# BMI088.net
KiCad netlist of a schematic drawn in Altium Designer
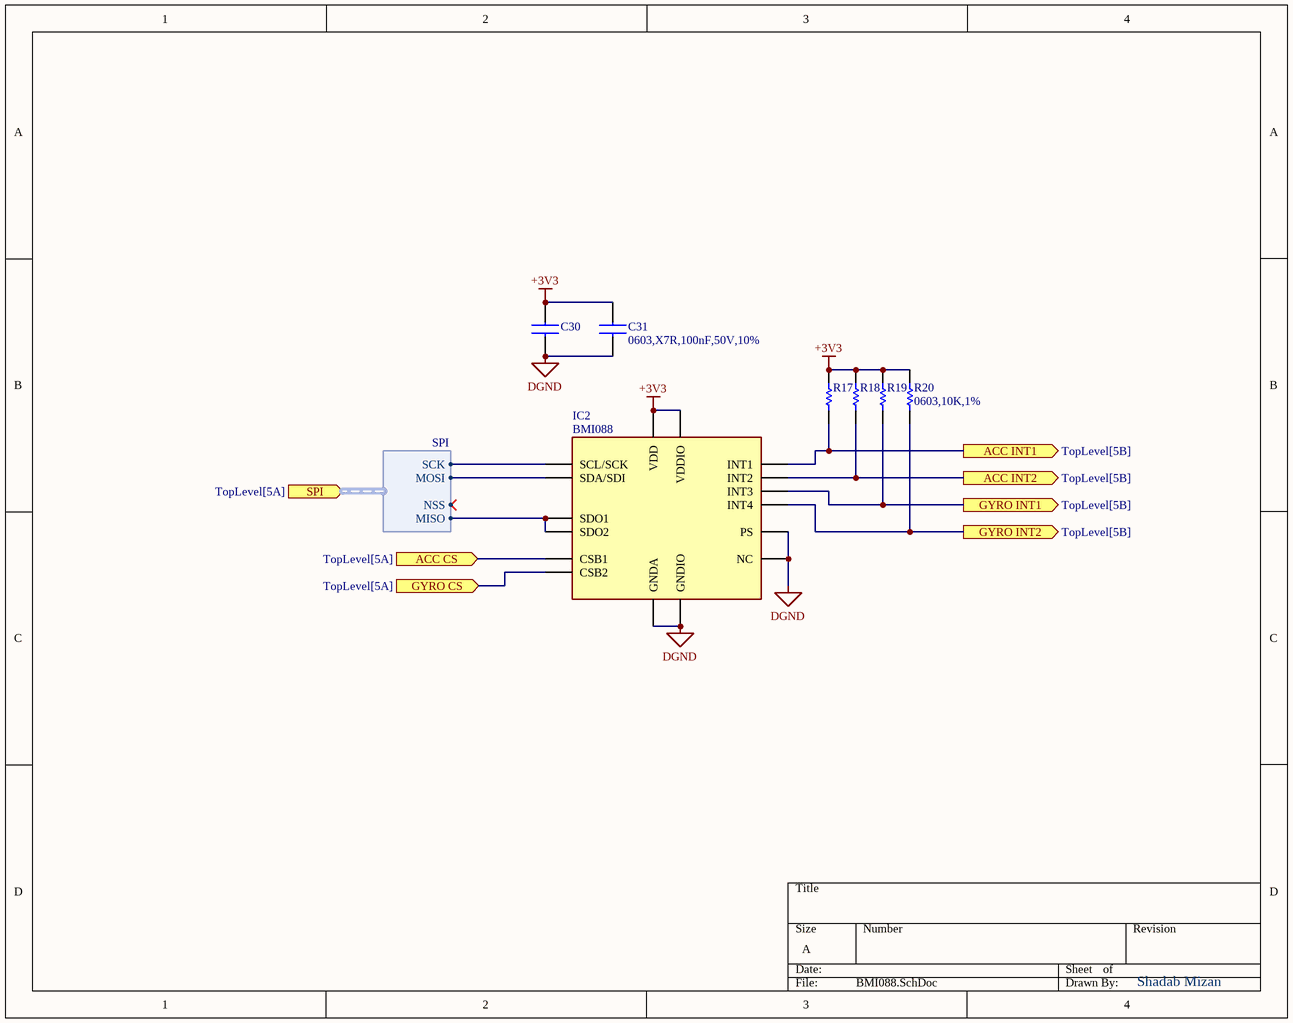
[diagram p0: BMI088.SchDoc]

(export (version "E")
  (design (tool "Eeschema 10.0.6"))
  (components
    (comp (ref "C30")
      (value "0603,X7R,100nF,50V,10%")
      (footprint "CAPC1608X90N")
      (description "50V 100nF X7R ±10% 0603 Multilayer Ceramic Capacitors MLCC - SMD/SMT ROHS")
      (fields (field (name "LCSC PART #") "C14663") (field (name "MANU PART #") "CC0603KRX7R9BB104"))
      (libsource (lib "flight-controller") (part "CC0603KRX7R9BB104"))
    )
    (comp (ref "C31")
      (value "0603,X7R,100nF,50V,10%")
      (footprint "CAPC1608X90N")
      (description "50V 100nF X7R ±10% 0603 Multilayer Ceramic Capacitors MLCC - SMD/SMT ROHS")
      (fields (field (name "LCSC PART #") "C14663") (field (name "MANU PART #") "CC0603KRX7R9BB104"))
      (libsource (lib "flight-controller") (part "CC0603KRX7R9BB104"))
    )
    (comp (ref "IC2")
      (value "BMI088")
      (footprint "BMI088")
      (description "Inertial Measurement Unit IMU 6-Axis LGA")
      (fields (field (name "LCSC PART #") "C194919"))
      (libsource (lib "flight-controller") (part "BMI088"))
    )
    (comp (ref "R17")
      (value "0603,10K,1%")
      (footprint "RESC1608X90N")
      (description "100mW Thick Film Resistor 75V ±100ppm/℃ ±1% 10kΩ 0603 Chip Resistor - Surface Mount ROHS")
      (fields (field (name "LCSC PART #") "C25804") (field (name "MANU PART #") "0603WAF1002T5E"))
      (libsource (lib "flight-controller") (part "0603WAF1002T5E"))
    )
    (comp (ref "R18")
      (value "0603,10K,1%")
      (footprint "RESC1608X90N")
      (description "100mW Thick Film Resistor 75V ±100ppm/℃ ±1% 10kΩ 0603 Chip Resistor - Surface Mount ROHS")
      (fields (field (name "LCSC PART #") "C25804") (field (name "MANU PART #") "0603WAF1002T5E"))
      (libsource (lib "flight-controller") (part "0603WAF1002T5E"))
    )
    (comp (ref "R19")
      (value "0603,10K,1%")
      (footprint "RESC1608X90N")
      (description "100mW Thick Film Resistor 75V ±100ppm/℃ ±1% 10kΩ 0603 Chip Resistor - Surface Mount ROHS")
      (fields (field (name "LCSC PART #") "C25804") (field (name "MANU PART #") "0603WAF1002T5E"))
      (libsource (lib "flight-controller") (part "0603WAF1002T5E"))
    )
    (comp (ref "R20")
      (value "0603,10K,1%")
      (footprint "RESC1608X90N")
      (description "100mW Thick Film Resistor 75V ±100ppm/℃ ±1% 10kΩ 0603 Chip Resistor - Surface Mount ROHS")
      (fields (field (name "LCSC PART #") "C25804") (field (name "MANU PART #") "0603WAF1002T5E"))
      (libsource (lib "flight-controller") (part "0603WAF1002T5E"))
    )
  )
  (nets
    (net (code "2") (name "+3V3") (class "Default")
      (node (ref "C30") (pin "2") (pinfunction "2_2") (pintype "passive"))
      (node (ref "C31") (pin "2") (pinfunction "2_2") (pintype "passive"))
      (node (ref "IC2") (pin "11") (pinfunction "VDDIO_11") (pintype "passive"))
      (node (ref "IC2") (pin "3") (pinfunction "VDD_3") (pintype "passive"))
      (node (ref "R17") (pin "2") (pinfunction "2_2") (pintype "passive"))
      (node (ref "R18") (pin "2") (pinfunction "2_2") (pintype "passive"))
      (node (ref "R19") (pin "2") (pinfunction "2_2") (pintype "passive"))
      (node (ref "R20") (pin "2") (pinfunction "2_2") (pintype "passive"))
    )
    (net (code "3") (name "/ACC CS") (class "Default")
      (node (ref "IC2") (pin "14") (pinfunction "CSB1_14") (pintype "passive"))
    )
    (net (code "4") (name "/ACC INT1") (class "Default")
      (node (ref "IC2") (pin "16") (pinfunction "INT1_16") (pintype "passive"))
      (node (ref "R17") (pin "1") (pinfunction "1_1") (pintype "passive"))
    )
    (net (code "5") (name "/ACC INT2") (class "Default")
      (node (ref "IC2") (pin "1") (pinfunction "INT2_1") (pintype "passive"))
      (node (ref "R18") (pin "1") (pinfunction "1_1") (pintype "passive"))
    )
    (net (code "6") (name "/GYRO CS") (class "Default")
      (node (ref "IC2") (pin "5") (pinfunction "CSB2_5") (pintype "passive"))
    )
    (net (code "7") (name "/GYRO INT1") (class "Default")
      (node (ref "IC2") (pin "12") (pinfunction "INT3_12") (pintype "passive"))
      (node (ref "R19") (pin "1") (pinfunction "1_1") (pintype "passive"))
    )
    (net (code "8") (name "/GYRO INT2") (class "Default")
      (node (ref "IC2") (pin "13") (pinfunction "INT4_13") (pintype "passive"))
      (node (ref "R20") (pin "1") (pinfunction "1_1") (pintype "passive"))
    )
    (net (code "9") (name "/MISO") (class "Default")
      (node (ref "IC2") (pin "10") (pinfunction "SDO2_10") (pintype "passive"))
      (node (ref "IC2") (pin "15") (pinfunction "SDO1_15") (pintype "passive"))
    )
    (net (code "10") (name "/MOSI") (class "Default")
      (node (ref "IC2") (pin "9") (pinfunction "SDA/SDI_9") (pintype "passive"))
    )
    (net (code "11") (name "/SCK") (class "Default")
      (node (ref "IC2") (pin "8") (pinfunction "SCL/SCK_8") (pintype "passive"))
    )
    (net (code "13") (name "DGND") (class "Default")
      (node (ref "C30") (pin "1") (pinfunction "1_1") (pintype "passive"))
      (node (ref "C31") (pin "1") (pinfunction "1_1") (pintype "passive"))
      (node (ref "IC2") (pin "2") (pinfunction "NC_2") (pintype "passive"))
      (node (ref "IC2") (pin "4") (pinfunction "GNDA_4") (pintype "passive"))
      (node (ref "IC2") (pin "6") (pinfunction "GNDIO_6") (pintype "passive"))
      (node (ref "IC2") (pin "7") (pinfunction "PS_7") (pintype "passive"))
    )
  )
)
